# STM32_USB-C.net
KiCad netlist of a schematic drawn in Altium Designer
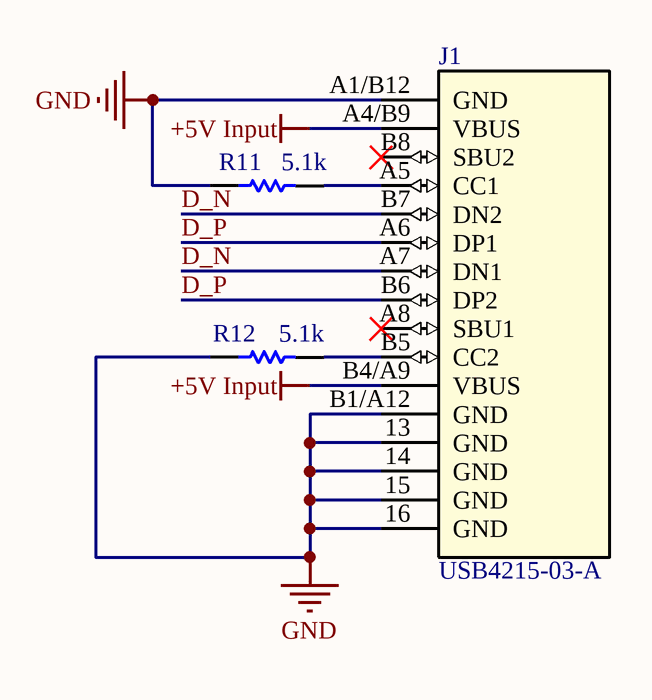
[diagram p0: STM32_USB-C.SchDoc]

(export (version "E")
  (design (tool "Eeschema 10.0.6"))
  (components
    (comp (ref "J1")
      (value "USB4215-03-A")
      (footprint "CONN_8p94X6p5X3p16_12L_GCC")
      (description "Description")
      (fields (field (name "COPYRIGHT") "Copyright (C) 2025 Ultra Librarian. All rights reserved."))
      (libsource (lib "Schlib1") (part "USB4215-03-A"))
    )
    (comp (ref "R11")
      (value "RC0603JR-075K1L")
      (footprint "RESC1608X55X25LL10T15")
      (description "Chip Resistor, 5.1 KOhm, +/- 5%, 0.1 W, -55 to 155 degC, 0603 (1608 Metric), RoHS, Tape and Reel")
      (fields
        (field (name "TOLERANCE") "5%")
        (field (name "RESISTANCE") "5.1k")
        (field (name "MANUFACTURER") "Yageo")
      )
      (libsource (lib "Altium Content Vault") (part "RES-2"))
    )
    (comp (ref "R12")
      (value "RC0603JR-075K1L")
      (footprint "RESC1608X55X25LL10T15")
      (description "Chip Resistor, 5.1 KOhm, +/- 5%, 0.1 W, -55 to 155 degC, 0603 (1608 Metric), RoHS, Tape and Reel")
      (fields
        (field (name "TOLERANCE") "5%")
        (field (name "RESISTANCE") "5.1k")
        (field (name "MANUFACTURER") "Yageo")
      )
      (libsource (lib "Altium Content Vault") (part "RES-2"))
    )
  )
  (nets
    (net (code "1") (name "+5V Input") (class "Default")
      (node (ref "J1") (pin "A4/B9") (pinfunction "VBUS_A4/B9") (pintype "passive"))
      (node (ref "J1") (pin "B4/A9") (pinfunction "VBUS_B4/A9") (pintype "passive"))
    )
    (net (code "2") (name "/D_N") (class "Default")
      (node (ref "J1") (pin "A7") (pinfunction "DN1_A7") (pintype "bidirectional"))
      (node (ref "J1") (pin "B7") (pinfunction "DN2_B7") (pintype "bidirectional"))
    )
    (net (code "3") (name "/D_P") (class "Default")
      (node (ref "J1") (pin "A6") (pinfunction "DP1_A6") (pintype "bidirectional"))
      (node (ref "J1") (pin "B6") (pinfunction "DP2_B6") (pintype "bidirectional"))
    )
    (net (code "4") (name "GND") (class "Default")
      (node (ref "J1") (pin "13") (pinfunction "GND_13") (pintype "power_in"))
      (node (ref "J1") (pin "14") (pinfunction "GND_14") (pintype "power_in"))
      (node (ref "J1") (pin "15") (pinfunction "GND_15") (pintype "power_in"))
      (node (ref "J1") (pin "16") (pinfunction "GND_16") (pintype "power_in"))
      (node (ref "J1") (pin "A1/B12") (pinfunction "GND_A1/B12") (pintype "power_in"))
      (node (ref "J1") (pin "B1/A12") (pinfunction "GND_B1/A12") (pintype "power_in"))
      (node (ref "R11") (pin "1") (pinfunction "1_1") (pintype "passive"))
      (node (ref "R12") (pin "1") (pinfunction "1_1") (pintype "passive"))
    )
    (net (code "5") (name "Net-(J1-CC1)") (class "Default")
      (node (ref "J1") (pin "A5") (pinfunction "CC1_A5") (pintype "bidirectional"))
      (node (ref "R11") (pin "2") (pinfunction "2_2") (pintype "passive"))
    )
    (net (code "6") (name "Net-(J1-CC2)") (class "Default")
      (node (ref "J1") (pin "B5") (pinfunction "CC2_B5") (pintype "bidirectional"))
      (node (ref "R12") (pin "2") (pinfunction "2_2") (pintype "passive"))
    )
    (net (code "7") (name "unconnected-(J1-SBU1-PadA8)") (class "Default")
      (node (ref "J1") (pin "A8") (pinfunction "SBU1_A8") (pintype "bidirectional+no_connect"))
    )
    (net (code "8") (name "unconnected-(J1-SBU2-PadB8)") (class "Default")
      (node (ref "J1") (pin "B8") (pinfunction "SBU2_B8") (pintype "bidirectional+no_connect"))
    )
  )
)
